# 08_USB3_0-RGMII.net
KiCad netlist of a schematic drawn in Altium Designer
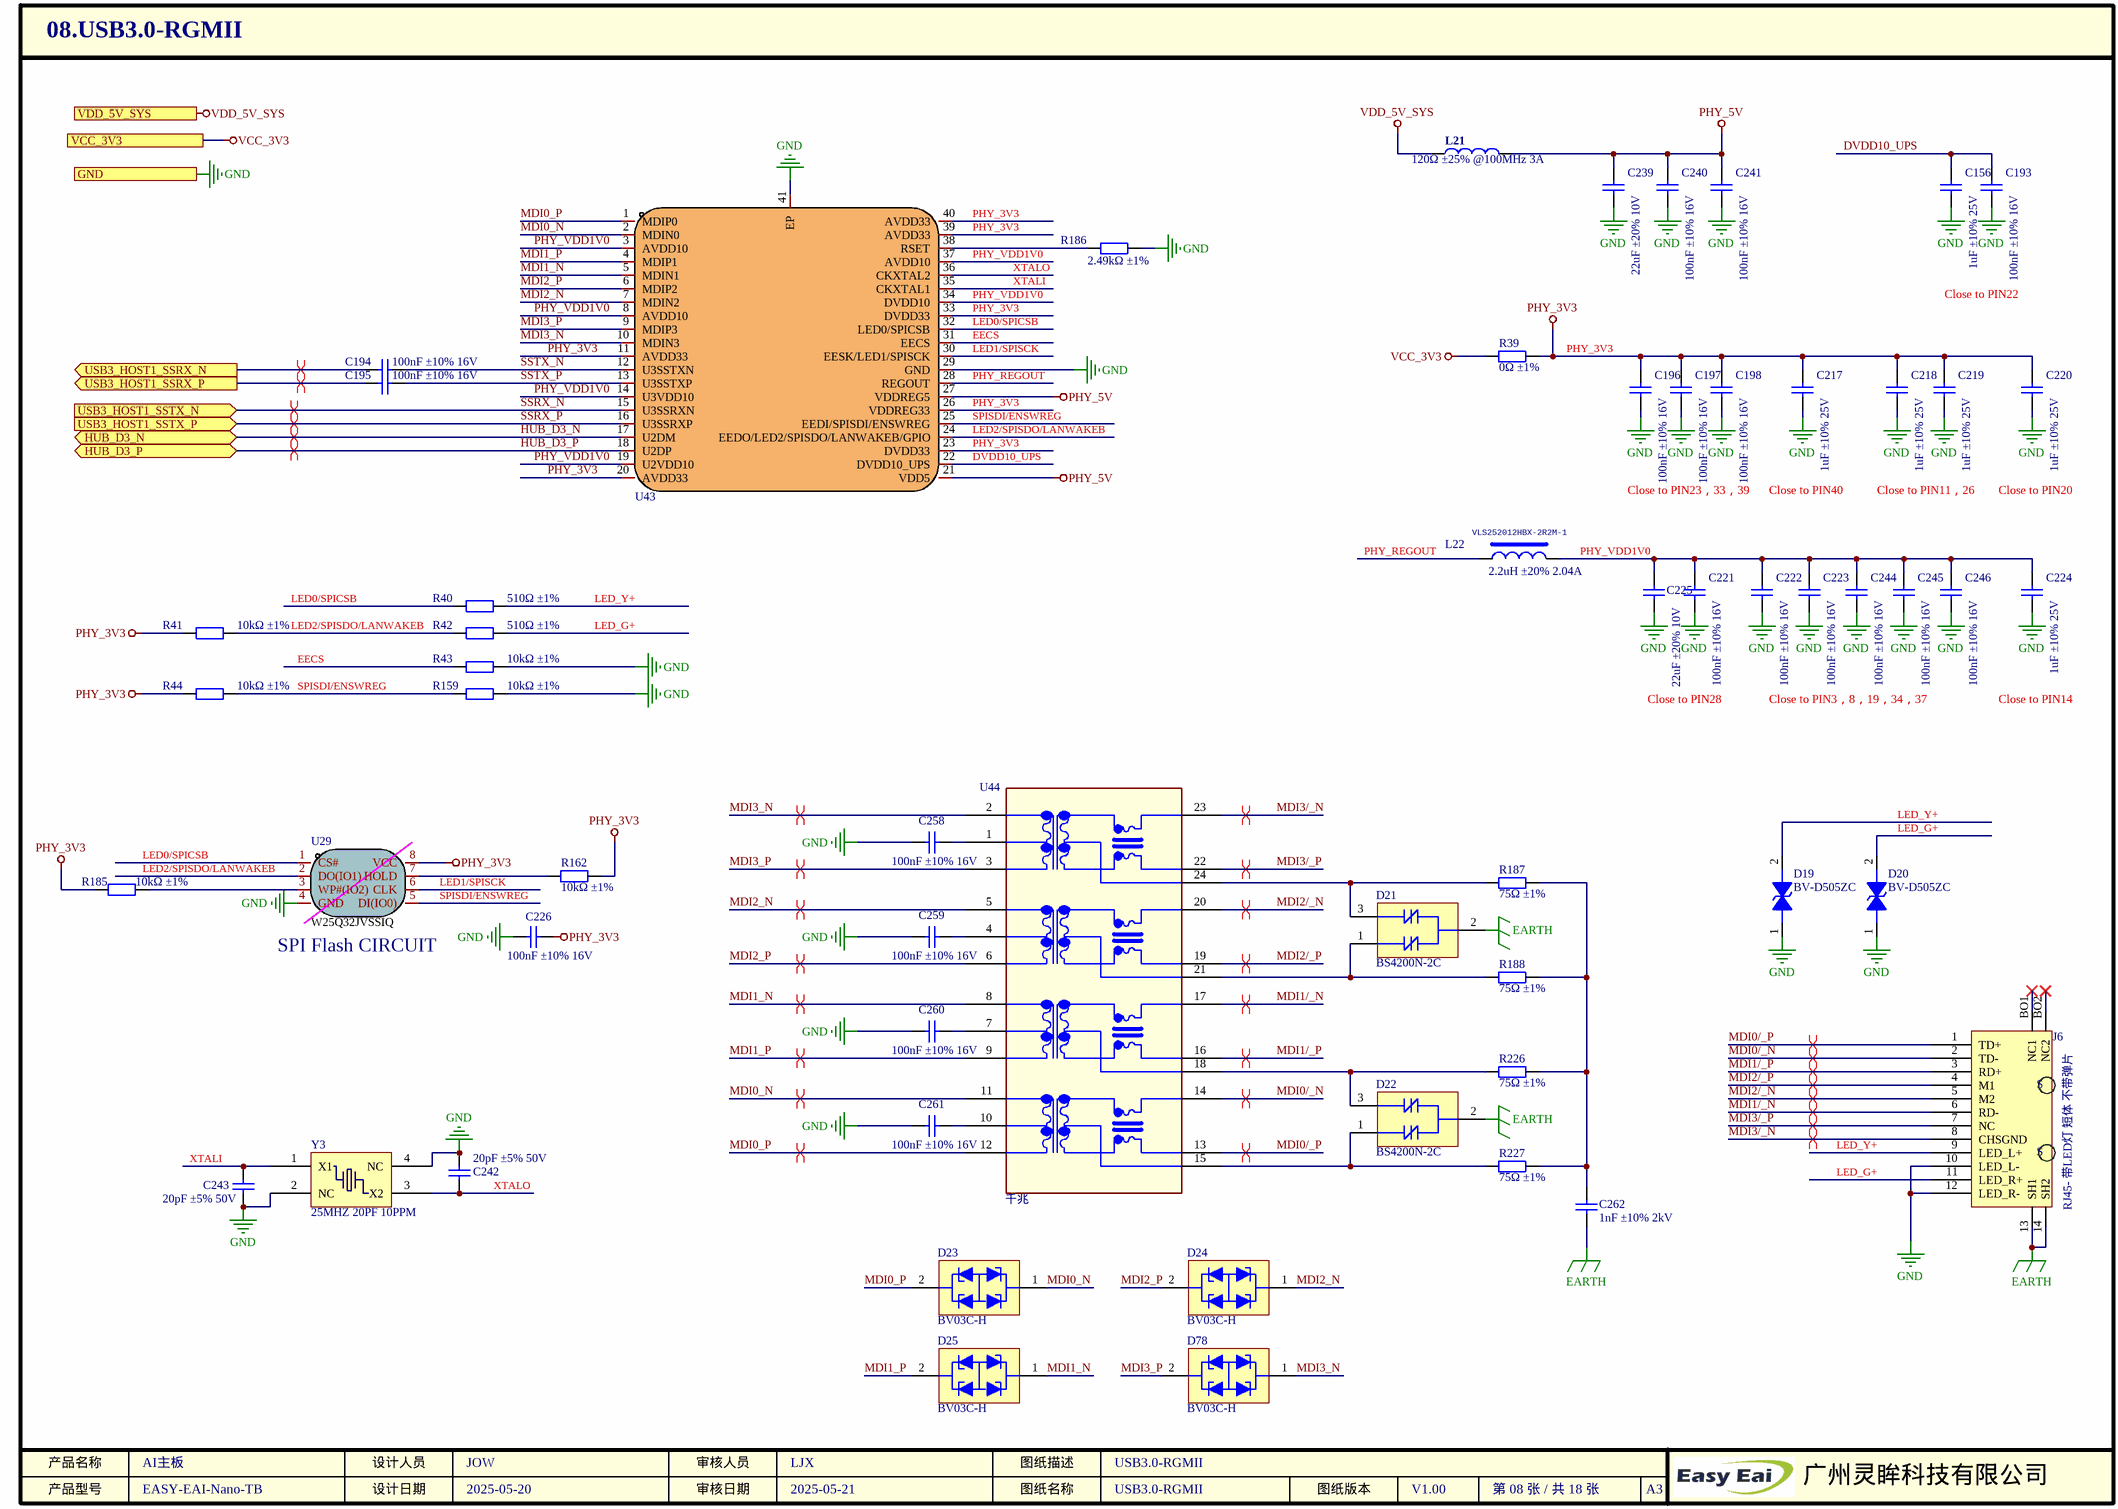
[diagram p0: 08.USB3.0-RGMII.SchDoc]

(export (version "E")
  (design (tool "Eeschema 10.0.6"))
  (components
    (comp (ref "C156")
      (value "CL05A105KA5NQNC")
      (footprint "0402_C")
      (description "SPZL000337")
      (fields (field (name "描述") "1uF ±10% 25V"))
      (libsource (lib "CAP_EASY-EAI") (part "0402 1uF ±10% 25V"))
    )
    (comp (ref "C193")
      (value "CL05B104KO5NNNC")
      (footprint "0402_C")
      (description "SPZL000259")
      (fields (field (name "描述") "100nF ±10% 16V"))
      (libsource (lib "CAP_lexing") (part "0402 100nF ±10% 16V"))
    )
    (comp (ref "C194")
      (value "CL05B104KO5NNNC")
      (footprint "0402_C")
      (description "SPZL000259")
      (fields (field (name "描述") "100nF ±10% 16V"))
      (libsource (lib "CAP_lexing") (part "0402 100nF ±10% 16V"))
    )
    (comp (ref "C195")
      (value "CL05B104KO5NNNC")
      (footprint "0402_C")
      (description "SPZL000259")
      (fields (field (name "描述") "100nF ±10% 16V"))
      (libsource (lib "CAP_lexing") (part "0402 100nF ±10% 16V"))
    )
    (comp (ref "C196")
      (value "CL05B104KO5NNNC")
      (footprint "0402_C")
      (description "SPZL000259")
      (fields (field (name "描述") "100nF ±10% 16V"))
      (libsource (lib "CAP_lexing") (part "0402 100nF ±10% 16V"))
    )
    (comp (ref "C197")
      (value "CL05B104KO5NNNC")
      (footprint "0402_C")
      (description "SPZL000259")
      (fields (field (name "描述") "100nF ±10% 16V"))
      (libsource (lib "CAP_lexing") (part "0402 100nF ±10% 16V"))
    )
    (comp (ref "C198")
      (value "CL05B104KO5NNNC")
      (footprint "0402_C")
      (description "SPZL000259")
      (fields (field (name "描述") "100nF ±10% 16V"))
      (libsource (lib "CAP_lexing") (part "0402 100nF ±10% 16V"))
    )
    (comp (ref "C217")
      (value "CL05A105KA5NQNC")
      (footprint "0402_C")
      (description "SPZL000337")
      (fields (field (name "描述") "1uF ±10% 25V"))
      (libsource (lib "CAP_EASY-EAI") (part "0402 1uF ±10% 25V"))
    )
    (comp (ref "C218")
      (value "CL05A105KA5NQNC")
      (footprint "0402_C")
      (description "SPZL000337")
      (fields (field (name "描述") "1uF ±10% 25V"))
      (libsource (lib "CAP_EASY-EAI") (part "0402 1uF ±10% 25V"))
    )
    (comp (ref "C219")
      (value "CL05A105KA5NQNC")
      (footprint "0402_C")
      (description "SPZL000337")
      (fields (field (name "描述") "1uF ±10% 25V"))
      (libsource (lib "CAP_EASY-EAI") (part "0402 1uF ±10% 25V"))
    )
    (comp (ref "C220")
      (value "CL05A105KA5NQNC")
      (footprint "0402_C")
      (description "SPZL000337")
      (fields (field (name "描述") "1uF ±10% 25V"))
      (libsource (lib "CAP_EASY-EAI") (part "0402 1uF ±10% 25V"))
    )
    (comp (ref "C221")
      (value "CL05B104KO5NNNC")
      (footprint "0402_C")
      (description "SPZL000259")
      (fields (field (name "描述") "100nF ±10% 16V"))
      (libsource (lib "CAP_lexing") (part "0402 100nF ±10% 16V"))
    )
    (comp (ref "C222")
      (value "CL05B104KO5NNNC")
      (footprint "0402_C")
      (description "SPZL000259")
      (fields (field (name "描述") "100nF ±10% 16V"))
      (libsource (lib "CAP_lexing") (part "0402 100nF ±10% 16V"))
    )
    (comp (ref "C223")
      (value "CL05B104KO5NNNC")
      (footprint "0402_C")
      (description "SPZL000259")
      (fields (field (name "描述") "100nF ±10% 16V"))
      (libsource (lib "CAP_lexing") (part "0402 100nF ±10% 16V"))
    )
    (comp (ref "C224")
      (value "CL05A105KA5NQNC")
      (footprint "0402_C")
      (description "SPZL000337")
      (fields (field (name "描述") "1uF ±10% 25V"))
      (libsource (lib "CAP_EASY-EAI") (part "0402 1uF ±10% 25V"))
    )
    (comp (ref "C225")
      (value "CL10A226MP8NUNE")
      (footprint "0603_C")
      (description "SPZL000315")
      (fields (field (name "描述") "22uF ±20% 10V"))
      (libsource (lib "CAP_lexing") (part "0603 22uF ±20% 10V"))
    )
    (comp (ref "C226")
      (value "CL05B104KO5NNNC")
      (footprint "0402_C")
      (description "SPZL000259")
      (fields (field (name "描述") "100nF ±10% 16V"))
      (libsource (lib "altium-import") (part "root_2_0402 100nF ±10% 16V_"))
    )
    (comp (ref "C239")
      (value "CL10A226MP8NUNE")
      (footprint "0603_C")
      (description "SPZL000315")
      (fields (field (name "描述") "22uF ±20% 10V"))
      (libsource (lib "CAP_lexing") (part "0603 22uF ±20% 10V"))
    )
    (comp (ref "C240")
      (value "CL05B104KO5NNNC")
      (footprint "0402_C")
      (description "SPZL000259")
      (fields (field (name "描述") "100nF ±10% 16V"))
      (libsource (lib "CAP_lexing") (part "0402 100nF ±10% 16V"))
    )
    (comp (ref "C241")
      (value "CL05B104KO5NNNC")
      (footprint "0402_C")
      (description "SPZL000259")
      (fields (field (name "描述") "100nF ±10% 16V"))
      (libsource (lib "CAP_lexing") (part "0402 100nF ±10% 16V"))
    )
    (comp (ref "C242")
      (value "0402CG200J500NT")
      (footprint "0402_C")
      (description "SPZL000398")
      (fields (field (name "描述") "20pF ±5% 50V"))
      (libsource (lib "CAP_lexing") (part "0402 20pF ±5% 50V"))
    )
    (comp (ref "C243")
      (value "0402CG200J500NT")
      (footprint "0402_C")
      (description "SPZL000398")
      (fields (field (name "描述") "20pF ±5% 50V"))
      (libsource (lib "CAP_lexing") (part "0402 20pF ±5% 50V"))
    )
    (comp (ref "C244")
      (value "CL05B104KO5NNNC")
      (footprint "0402_C")
      (description "SPZL000259")
      (fields (field (name "描述") "100nF ±10% 16V"))
      (libsource (lib "CAP_lexing") (part "0402 100nF ±10% 16V"))
    )
    (comp (ref "C245")
      (value "CL05B104KO5NNNC")
      (footprint "0402_C")
      (description "SPZL000259")
      (fields (field (name "描述") "100nF ±10% 16V"))
      (libsource (lib "CAP_lexing") (part "0402 100nF ±10% 16V"))
    )
    (comp (ref "C246")
      (value "CL05B104KO5NNNC")
      (footprint "0402_C")
      (description "SPZL000259")
      (fields (field (name "描述") "100nF ±10% 16V"))
      (libsource (lib "CAP_lexing") (part "0402 100nF ±10% 16V"))
    )
    (comp (ref "C258")
      (value "CL05B104KO5NNNC")
      (footprint "0402_C")
      (description "SPZL000259")
      (fields (field (name "描述") "100nF ±10% 16V"))
      (libsource (lib "CAP_lexing") (part "0402 100nF ±10% 16V"))
    )
    (comp (ref "C259")
      (value "CL05B104KO5NNNC")
      (footprint "0402_C")
      (description "SPZL000259")
      (fields (field (name "描述") "100nF ±10% 16V"))
      (libsource (lib "CAP_lexing") (part "0402 100nF ±10% 16V"))
    )
    (comp (ref "C260")
      (value "CL05B104KO5NNNC")
      (footprint "0402_C")
      (description "SPZL000259")
      (fields (field (name "描述") "100nF ±10% 16V"))
      (libsource (lib "CAP_lexing") (part "0402 100nF ±10% 16V"))
    )
    (comp (ref "C261")
      (value "CL05B104KO5NNNC")
      (footprint "0402_C")
      (description "SPZL000259")
      (fields (field (name "描述") "100nF ±10% 16V"))
      (libsource (lib "CAP_lexing") (part "0402 100nF ±10% 16V"))
    )
    (comp (ref "C262")
      (value "CC1206KKX7RDBB102")
      (footprint "1206_C")
      (description "SPZL000332")
      (fields (field (name "描述") "1nF ±10% 2kV"))
      (libsource (lib "CAP_lexing") (part "1206 1nF ±10% 2kV"))
    )
    (comp (ref "D19")
      (value "BV-D505ZC")
      (footprint "SOD-523")
      (description "SPZL000613")
      (fields (field (name "型号") "BV-D505ZC"))
      (libsource (lib "ESD_lexing") (part "ESD BV-D505ZC"))
    )
    (comp (ref "D20")
      (value "BV-D505ZC")
      (footprint "SOD-523")
      (description "SPZL000613")
      (fields (field (name "型号") "BV-D505ZC"))
      (libsource (lib "ESD_lexing") (part "ESD BV-D505ZC"))
    )
    (comp (ref "D21")
      (value "BS4200N-2C")
      (footprint "SMB-T_L5.4-W3.3-BI")
      (description "SPZL000612")
      (fields (field (name "型号") "BS4200N-2C"))
      (libsource (lib "ESD_lexing") (part "放电管 BS4200N-2C"))
    )
    (comp (ref "D22")
      (value "BS4200N-2C")
      (footprint "SMB-T_L5.4-W3.3-BI")
      (description "SPZL000612")
      (fields (field (name "型号") "BS4200N-2C"))
      (libsource (lib "ESD_lexing") (part "放电管 BS4200N-2C"))
    )
    (comp (ref "D23")
      (value "BV03C-H")
      (footprint "SOD-323")
      (description "SPZL000614")
      (fields (field (name "型号") "BV03C-H"))
      (libsource (lib "ESD_lexing") (part "ESD BV03C-H"))
    )
    (comp (ref "D24")
      (value "BV03C-H")
      (footprint "SOD-323")
      (description "SPZL000614")
      (fields (field (name "型号") "BV03C-H"))
      (libsource (lib "ESD_lexing") (part "ESD BV03C-H"))
    )
    (comp (ref "D25")
      (value "BV03C-H")
      (footprint "SOD-323")
      (description "SPZL000614")
      (fields (field (name "型号") "BV03C-H"))
      (libsource (lib "ESD_lexing") (part "ESD BV03C-H"))
    )
    (comp (ref "D78")
      (value "BV03C-H")
      (footprint "SOD-323")
      (description "SPZL000614")
      (fields (field (name "型号") "BV03C-H"))
      (libsource (lib "ESD_lexing") (part "ESD BV03C-H"))
    )
    (comp (ref "J6")
      (value "R-RJ45R08P-C000")
      (footprint "RJ45/LED-1575X1626X1310")
      (description "SPZL000140")
      (fields (field (name "描述") "RJ45- 带LED灯 短体 不带弹片"))
      (libsource (lib "EVBoard-RK3562") (part "RJ45- 带LED灯 短体 不带弹片"))
    )
    (comp (ref "L21")
      (value "BLM18KG121TN1D")
      (footprint "0603_R")
      (description "SPZL000842")
      (fields (field (name "描述") "120Ω ±25% @100MHz 3A"))
      (libsource (lib "Inductor_EASY-EAI") (part "120Ω ±25% @100MHz 3A"))
    )
    (comp (ref "L22")
      (value "VLS252012HBX-2R2M-1")
      (footprint "IND_252012")
      (description "SPZL000205")
      (fields (field (name "描述") "2.2uH ±20% 2.04A"))
      (libsource (lib "Inductor_EASY-EAI") (part "2.2uH ±20% 2.04A"))
    )
    (comp (ref "R39")
      (value "0805W8F0000T5E")
      (footprint "0805_R")
      (description "SPZL000350")
      (fields (field (name "描述") "0Ω ±1%"))
      (libsource (lib "RES_EASY-EAI") (part "0805 0Ω ±1%"))
    )
    (comp (ref "R40")
      (value "0402WGF5100TCE")
      (footprint "0402_R")
      (description "SPZL000335")
      (fields (field (name "描述") "510Ω ±1%"))
      (libsource (lib "RES_lexing") (part "0402 510Ω ±1%"))
    )
    (comp (ref "R41")
      (value "0402WGF1002TCE")
      (footprint "0402_R")
      (description "SPZL000271")
      (fields (field (name "描述") "10kΩ ±1%"))
      (libsource (lib "RES_EASY-EAI") (part "0402 10kΩ ±1%"))
    )
    (comp (ref "R42")
      (value "0402WGF5100TCE")
      (footprint "0402_R")
      (description "SPZL000335")
      (fields (field (name "描述") "510Ω ±1%"))
      (libsource (lib "RES_lexing") (part "0402 510Ω ±1%"))
    )
    (comp (ref "R43")
      (value "0402WGF1002TCE")
      (footprint "0402_R")
      (description "SPZL000271")
      (fields (field (name "描述") "10kΩ ±1%"))
      (libsource (lib "RES_EASY-EAI") (part "0402 10kΩ ±1%"))
    )
    (comp (ref "R44")
      (value "0402WGF1002TCE")
      (footprint "0402_R")
      (description "SPZL000271")
      (fields (field (name "描述") "10kΩ ±1%"))
      (libsource (lib "RES_EASY-EAI") (part "0402 10kΩ ±1%"))
    )
    (comp (ref "R159")
      (value "0402WGF1002TCE")
      (footprint "0402_R")
      (description "SPZL000271")
      (fields (field (name "描述") "10kΩ ±1%"))
      (libsource (lib "RES_EASY-EAI") (part "0402 10kΩ ±1%"))
    )
    (comp (ref "R162")
      (value "0402WGF1002TCE")
      (footprint "0402_R")
      (description "SPZL000271")
      (fields (field (name "描述") "10kΩ ±1%"))
      (libsource (lib "") (part "0402 10kΩ ±1%_1"))
    )
    (comp (ref "R185")
      (value "0402WGF1002TCE")
      (footprint "0402_R")
      (description "SPZL000271")
      (fields (field (name "描述") "10kΩ ±1%"))
      (libsource (lib "RES_EASY-EAI") (part "0402 10kΩ ±1%"))
    )
    (comp (ref "R186")
      (value "AC0402FR-072K49L")
      (footprint "0402_R")
      (description "SPZL000354")
      (fields (field (name "描述") "2.49kΩ ±1%"))
      (libsource (lib "RES_lexing") (part "0402 2.49kΩ ±1%"))
    )
    (comp (ref "R187")
      (value "RS-05K75R0FT")
      (footprint "0805_R")
      (description "SPZL000353")
      (fields (field (name "描述") "75Ω ±1%"))
      (libsource (lib "RES_lexing") (part "0805 75Ω ±1%"))
    )
    (comp (ref "R188")
      (value "RS-05K75R0FT")
      (footprint "0805_R")
      (description "SPZL000353")
      (fields (field (name "描述") "75Ω ±1%"))
      (libsource (lib "RES_lexing") (part "0805 75Ω ±1%"))
    )
    (comp (ref "R226")
      (value "RS-05K75R0FT")
      (footprint "0805_R")
      (description "SPZL000353")
      (fields (field (name "描述") "75Ω ±1%"))
      (libsource (lib "RES_lexing") (part "0805 75Ω ±1%"))
    )
    (comp (ref "R227")
      (value "RS-05K75R0FT")
      (footprint "0805_R")
      (description "SPZL000353")
      (fields (field (name "描述") "75Ω ±1%"))
      (libsource (lib "RES_lexing") (part "0805 75Ω ±1%"))
    )
    (comp (ref "U29")
      (value "W25Q32JVSSIQ")
      (footprint "SOIC-8-208mil")
      (description "SPZL001045")
      (fields (field (name "型号") "W25Q32JVSSIQ"))
      (libsource (lib "IC_EASY-EAI") (part "W25Q32JVSSIQ"))
    )
    (comp (ref "U43")
      (value "RTL8153B-VB-CG")
      (footprint "QFN-40_L5.0-W5.0-P0.40-BL-EP3.7")
      (description "SPZL001044")
      (libsource (lib "IC_lexing") (part "RTL8153B-VB-CG"))
    )
    (comp (ref "U44")
      (value "G2401CE")
      (footprint "SMD-24_L15.1-W7.1-P1.00-LS10.0-BL")
      (description "SPZL000720")
      (fields (field (name "描述") "千兆"))
      (libsource (lib "ESD_lexing") (part "网络变压器 G2401CE"))
    )
    (comp (ref "Y3")
      (value "X322525MSB4SI")
      (footprint "SMD-3225_4P")
      (description "SPZL000475")
      (fields (field (name "描述") "25MHZ 20PF 10PPM"))
      (libsource (lib "XTAL_lexing") (part "25MHZ 20PF 10PPM"))
    )
  )
  (nets
    (net (code "1") (name "/DVDD10_UPS") (class "Default")
      (node (ref "C156") (pin "2") (pinfunction "2_2") (pintype "passive"))
      (node (ref "C193") (pin "2") (pinfunction "2_2") (pintype "passive"))
      (node (ref "U43") (pin "22") (pinfunction "DVDD10_UPS_22") (pintype "passive"))
    )
    (net (code "2") (name "/EECS") (class "Default")
      (node (ref "R43") (pin "2") (pinfunction "2_2") (pintype "passive"))
      (node (ref "U43") (pin "31") (pinfunction "EECS_31") (pintype "passive"))
    )
    (net (code "3") (name "/HUB_D3_N") (class "Default")
      (node (ref "U43") (pin "17") (pinfunction "U2DM_17") (pintype "passive"))
    )
    (net (code "4") (name "/HUB_D3_P") (class "Default")
      (node (ref "U43") (pin "18") (pinfunction "U2DP_18") (pintype "passive"))
    )
    (net (code "5") (name "/LED0{slash}SPICSB") (class "Default")
      (node (ref "R40") (pin "1") (pinfunction "1_1") (pintype "passive"))
      (node (ref "U29") (pin "1") (pinfunction "CS#_1") (pintype "passive"))
      (node (ref "U43") (pin "32") (pinfunction "LED0/SPICSB_32") (pintype "passive"))
    )
    (net (code "6") (name "/LED1{slash}SPISCK") (class "Default")
      (node (ref "U29") (pin "6") (pinfunction "CLK_6") (pintype "passive"))
      (node (ref "U43") (pin "30") (pinfunction "EESK/LED1/SPISCK_30") (pintype "passive"))
    )
    (net (code "7") (name "/LED2{slash}SPISDO{slash}LANWAKEB") (class "Default")
      (node (ref "R41") (pin "1") (pinfunction "1_1") (pintype "passive"))
      (node (ref "R42") (pin "1") (pinfunction "1_1") (pintype "passive"))
      (node (ref "U29") (pin "2") (pinfunction "DO(IO1)_2") (pintype "passive"))
      (node (ref "U43") (pin "24") (pinfunction "EEDO/LED2/SPISDO/LANWAKEB/GPIO_24") (pintype "passive"))
    )
    (net (code "8") (name "/LED_G+") (class "Default")
      (node (ref "D20") (pin "2") (pinfunction "2_2") (pintype "passive"))
      (node (ref "J6") (pin "11") (pinfunction "LED_R+_11") (pintype "passive"))
      (node (ref "R42") (pin "2") (pinfunction "2_2") (pintype "passive"))
    )
    (net (code "9") (name "/LED_Y+") (class "Default")
      (node (ref "D19") (pin "2") (pinfunction "2_2") (pintype "passive"))
      (node (ref "J6") (pin "9") (pinfunction "LED_L+_9") (pintype "passive"))
      (node (ref "R40") (pin "2") (pinfunction "2_2") (pintype "passive"))
    )
    (net (code "10") (name "/MDI0_N") (class "Default")
      (node (ref "D23") (pin "1") (pintype "passive"))
      (node (ref "U43") (pin "2") (pinfunction "MDIN0_2") (pintype "passive"))
      (node (ref "U44") (pin "11") (pinfunction "11_11") (pintype "passive"))
    )
    (net (code "11") (name "/MDI0_P") (class "Default")
      (node (ref "D23") (pin "2") (pintype "passive"))
      (node (ref "U43") (pin "1") (pinfunction "MDIP0_1") (pintype "passive"))
      (node (ref "U44") (pin "12") (pinfunction "12_12") (pintype "passive"))
    )
    (net (code "12") (name "/MDI0{slash}_N") (class "Default")
      (node (ref "J6") (pin "2") (pinfunction "TD-_2") (pintype "passive"))
      (node (ref "U44") (pin "14") (pinfunction "14_14") (pintype "passive"))
    )
    (net (code "13") (name "/MDI0{slash}_P") (class "Default")
      (node (ref "J6") (pin "1") (pinfunction "TD+_1") (pintype "passive"))
      (node (ref "U44") (pin "13") (pinfunction "13_13") (pintype "passive"))
    )
    (net (code "14") (name "/MDI1_N") (class "Default")
      (node (ref "D25") (pin "1") (pintype "passive"))
      (node (ref "U43") (pin "5") (pinfunction "MDIN1_5") (pintype "passive"))
      (node (ref "U44") (pin "8") (pinfunction "8_8") (pintype "passive"))
    )
    (net (code "15") (name "/MDI1_P") (class "Default")
      (node (ref "D25") (pin "2") (pintype "passive"))
      (node (ref "U43") (pin "4") (pinfunction "MDIP1_4") (pintype "passive"))
      (node (ref "U44") (pin "9") (pinfunction "9_9") (pintype "passive"))
    )
    (net (code "16") (name "/MDI1{slash}_N") (class "Default")
      (node (ref "J6") (pin "6") (pinfunction "RD-_6") (pintype "passive"))
      (node (ref "U44") (pin "17") (pinfunction "17_17") (pintype "passive"))
    )
    (net (code "17") (name "/MDI1{slash}_P") (class "Default")
      (node (ref "J6") (pin "3") (pinfunction "RD+_3") (pintype "passive"))
      (node (ref "U44") (pin "16") (pinfunction "16_16") (pintype "passive"))
    )
    (net (code "18") (name "/MDI2_N") (class "Default")
      (node (ref "D24") (pin "1") (pintype "passive"))
      (node (ref "U43") (pin "7") (pinfunction "MDIN2_7") (pintype "passive"))
      (node (ref "U44") (pin "5") (pinfunction "5_5") (pintype "passive"))
    )
    (net (code "19") (name "/MDI2_P") (class "Default")
      (node (ref "D24") (pin "2") (pintype "passive"))
      (node (ref "U43") (pin "6") (pinfunction "MDIP2_6") (pintype "passive"))
      (node (ref "U44") (pin "6") (pinfunction "6_6") (pintype "passive"))
    )
    (net (code "20") (name "/MDI2{slash}_N") (class "Default")
      (node (ref "J6") (pin "5") (pinfunction "M2_5") (pintype "passive"))
      (node (ref "U44") (pin "20") (pinfunction "20_20") (pintype "passive"))
    )
    (net (code "21") (name "/MDI2{slash}_P") (class "Default")
      (node (ref "J6") (pin "4") (pinfunction "M1_4") (pintype "passive"))
      (node (ref "U44") (pin "19") (pinfunction "19_19") (pintype "passive"))
    )
    (net (code "22") (name "/MDI3_N") (class "Default")
      (node (ref "D78") (pin "1") (pintype "passive"))
      (node (ref "U43") (pin "10") (pinfunction "MDIN3_10") (pintype "passive"))
      (node (ref "U44") (pin "2") (pinfunction "2_2") (pintype "passive"))
    )
    (net (code "23") (name "/MDI3_P") (class "Default")
      (node (ref "D78") (pin "2") (pintype "passive"))
      (node (ref "U43") (pin "9") (pinfunction "MDIP3_9") (pintype "passive"))
      (node (ref "U44") (pin "3") (pinfunction "3_3") (pintype "passive"))
    )
    (net (code "24") (name "/MDI3{slash}_N") (class "Default")
      (node (ref "J6") (pin "8") (pinfunction "CHSGND_8") (pintype "passive"))
      (node (ref "U44") (pin "23") (pinfunction "23_23") (pintype "passive"))
    )
    (net (code "25") (name "/MDI3{slash}_P") (class "Default")
      (node (ref "J6") (pin "7") (pinfunction "NC_7") (pintype "passive"))
      (node (ref "U44") (pin "22") (pinfunction "22_22") (pintype "passive"))
    )
    (net (code "26") (name "/PHY_REGOUT") (class "Default")
      (node (ref "L22") (pin "1") (pinfunction "1_1") (pintype "passive"))
      (node (ref "U43") (pin "28") (pinfunction "REGOUT_28") (pintype "passive"))
    )
    (net (code "27") (name "/PHY_VDD1V0") (class "Default")
      (node (ref "C221") (pin "2") (pinfunction "2_2") (pintype "passive"))
      (node (ref "C222") (pin "2") (pinfunction "2_2") (pintype "passive"))
      (node (ref "C223") (pin "2") (pinfunction "2_2") (pintype "passive"))
      (node (ref "C224") (pin "2") (pinfunction "2_2") (pintype "passive"))
      (node (ref "C225") (pin "2") (pinfunction "2_2") (pintype "passive"))
      (node (ref "C244") (pin "2") (pinfunction "2_2") (pintype "passive"))
      (node (ref "C245") (pin "2") (pinfunction "2_2") (pintype "passive"))
      (node (ref "C246") (pin "2") (pinfunction "2_2") (pintype "passive"))
      (node (ref "L22") (pin "2") (pinfunction "2_2") (pintype "passive"))
      (node (ref "U43") (pin "14") (pinfunction "U3VDD10_14") (pintype "passive"))
      (node (ref "U43") (pin "19") (pinfunction "U2VDD10_19") (pintype "passive"))
      (node (ref "U43") (pin "3") (pinfunction "AVDD10_3") (pintype "passive"))
      (node (ref "U43") (pin "34") (pinfunction "DVDD10_34") (pintype "passive"))
      (node (ref "U43") (pin "37") (pinfunction "AVDD10_37") (pintype "passive"))
      (node (ref "U43") (pin "8") (pinfunction "AVDD10_8") (pintype "passive"))
    )
    (net (code "28") (name "/SPISDI{slash}ENSWREG") (class "Default")
      (node (ref "R159") (pin "2") (pinfunction "2_2") (pintype "passive"))
      (node (ref "R44") (pin "1") (pinfunction "1_1") (pintype "passive"))
      (node (ref "U29") (pin "5") (pinfunction "DI(IO0)_5") (pintype "passive"))
      (node (ref "U43") (pin "25") (pinfunction "EEDI/SPISDI/ENSWREG_25") (pintype "passive"))
    )
    (net (code "29") (name "/SSRX_N") (class "Default")
      (node (ref "U43") (pin "15") (pinfunction "U3SSRXN_15") (pintype "passive"))
    )
    (net (code "30") (name "/SSRX_P") (class "Default")
      (node (ref "U43") (pin "16") (pinfunction "U3SSRXP_16") (pintype "passive"))
    )
    (net (code "31") (name "/SSTX_N") (class "Default")
      (node (ref "C194") (pin "2") (pinfunction "2_2") (pintype "passive"))
      (node (ref "U43") (pin "12") (pinfunction "U3SSTXN_12") (pintype "passive"))
    )
    (net (code "32") (name "/SSTX_P") (class "Default")
      (node (ref "C195") (pin "2") (pinfunction "2_2") (pintype "passive"))
      (node (ref "U43") (pin "13") (pinfunction "U3SSTXP_13") (pintype "passive"))
    )
    (net (code "33") (name "/USB3_HOST1_SSRX_N") (class "Default")
      (node (ref "C194") (pin "1") (pinfunction "1_1") (pintype "passive"))
    )
    (net (code "34") (name "/USB3_HOST1_SSRX_P") (class "Default")
      (node (ref "C195") (pin "1") (pinfunction "1_1") (pintype "passive"))
    )
    (net (code "35") (name "/XTALI") (class "Default")
      (node (ref "C243") (pin "2") (pinfunction "2_2") (pintype "passive"))
      (node (ref "U43") (pin "35") (pinfunction "CKXTAL1_35") (pintype "passive"))
      (node (ref "Y3") (pin "1") (pinfunction "X1_1") (pintype "passive"))
    )
    (net (code "36") (name "/XTALO") (class "Default")
      (node (ref "C242") (pin "1") (pinfunction "1_1") (pintype "passive"))
      (node (ref "U43") (pin "36") (pinfunction "CKXTAL2_36") (pintype "passive"))
      (node (ref "Y3") (pin "3") (pinfunction "X2_3") (pintype "passive"))
    )
    (net (code "37") (name "EARTH") (class "Default")
      (node (ref "C262") (pin "1") (pinfunction "1_1") (pintype "passive"))
      (node (ref "D21") (pin "2") (pintype "passive"))
      (node (ref "D22") (pin "2") (pintype "passive"))
      (node (ref "J6") (pin "13") (pinfunction "SH1_13") (pintype "passive"))
      (node (ref "J6") (pin "14") (pinfunction "SH2_14") (pintype "passive"))
    )
    (net (code "38") (name "GND") (class "Default")
      (node (ref "C156") (pin "1") (pinfunction "1_1") (pintype "passive"))
      (node (ref "C193") (pin "1") (pinfunction "1_1") (pintype "passive"))
      (node (ref "C196") (pin "1") (pinfunction "1_1") (pintype "passive"))
      (node (ref "C197") (pin "1") (pinfunction "1_1") (pintype "passive"))
      (node (ref "C198") (pin "1") (pinfunction "1_1") (pintype "passive"))
      (node (ref "C217") (pin "1") (pinfunction "1_1") (pintype "passive"))
      (node (ref "C218") (pin "1") (pinfunction "1_1") (pintype "passive"))
      (node (ref "C219") (pin "1") (pinfunction "1_1") (pintype "passive"))
      (node (ref "C220") (pin "1") (pinfunction "1_1") (pintype "passive"))
      (node (ref "C221") (pin "1") (pinfunction "1_1") (pintype "passive"))
      (node (ref "C222") (pin "1") (pinfunction "1_1") (pintype "passive"))
      (node (ref "C223") (pin "1") (pinfunction "1_1") (pintype "passive"))
      (node (ref "C224") (pin "1") (pinfunction "1_1") (pintype "passive"))
      (node (ref "C225") (pin "1") (pinfunction "1_1") (pintype "passive"))
      (node (ref "C226") (pin "2") (pinfunction "2_2") (pintype "passive"))
      (node (ref "C239") (pin "1") (pinfunction "1_1") (pintype "passive"))
      (node (ref "C240") (pin "1") (pinfunction "1_1") (pintype "passive"))
      (node (ref "C241") (pin "1") (pinfunction "1_1") (pintype "passive"))
      (node (ref "C242") (pin "2") (pinfunction "2_2") (pintype "passive"))
      (node (ref "C243") (pin "1") (pinfunction "1_1") (pintype "passive"))
      (node (ref "C244") (pin "1") (pinfunction "1_1") (pintype "passive"))
      (node (ref "C245") (pin "1") (pinfunction "1_1") (pintype "passive"))
      (node (ref "C246") (pin "1") (pinfunction "1_1") (pintype "passive"))
      (node (ref "C258") (pin "1") (pinfunction "1_1") (pintype "passive"))
      (node (ref "C259") (pin "1") (pinfunction "1_1") (pintype "passive"))
      (node (ref "C260") (pin "1") (pinfunction "1_1") (pintype "passive"))
      (node (ref "C261") (pin "1") (pinfunction "1_1") (pintype "passive"))
      (node (ref "D19") (pin "1") (pinfunction "1_1") (pintype "passive"))
      (node (ref "D20") (pin "1") (pinfunction "1_1") (pintype "passive"))
      (node (ref "J6") (pin "10") (pinfunction "LED_L-_10") (pintype "passive"))
      (node (ref "J6") (pin "12") (pinfunction "LED_R-_12") (pintype "passive"))
      (node (ref "R159") (pin "1") (pinfunction "1_1") (pintype "passive"))
      (node (ref "R186") (pin "2") (pinfunction "2_2") (pintype "passive"))
      (node (ref "R43") (pin "1") (pinfunction "1_1") (pintype "passive"))
      (node (ref "U29") (pin "4") (pinfunction "GND_4") (pintype "passive"))
      (node (ref "U43") (pin "29") (pinfunction "GND_29") (pintype "passive"))
      (node (ref "U43") (pin "41") (pinfunction "EP_41") (pintype "passive"))
      (node (ref "Y3") (pin "2") (pinfunction "NC_2") (pintype "passive"))
      (node (ref "Y3") (pin "4") (pinfunction "NC_4") (pintype "passive"))
    )
    (net (code "39") (name "Net-(C258-Pad2)") (class "Default")
      (node (ref "C258") (pin "2") (pinfunction "2_2") (pintype "passive"))
      (node (ref "U44") (pin "1") (pinfunction "1_1") (pintype "passive"))
    )
    (net (code "40") (name "Net-(C259-Pad2)") (class "Default")
      (node (ref "C259") (pin "2") (pinfunction "2_2") (pintype "passive"))
      (node (ref "U44") (pin "4") (pinfunction "4_4") (pintype "passive"))
    )
    (net (code "41") (name "Net-(C260-Pad2)") (class "Default")
      (node (ref "C260") (pin "2") (pinfunction "2_2") (pintype "passive"))
      (node (ref "U44") (pin "7") (pinfunction "7_7") (pintype "passive"))
    )
    (net (code "42") (name "Net-(C261-Pad2)") (class "Default")
      (node (ref "C261") (pin "2") (pinfunction "2_2") (pintype "passive"))
      (node (ref "U44") (pin "10") (pinfunction "10_10") (pintype "passive"))
    )
    (net (code "43") (name "Net-(C262-Pad2)") (class "Default")
      (node (ref "C262") (pin "2") (pinfunction "2_2") (pintype "passive"))
      (node (ref "R187") (pin "2") (pinfunction "2_2") (pintype "passive"))
      (node (ref "R188") (pin "2") (pinfunction "2_2") (pintype "passive"))
      (node (ref "R226") (pin "2") (pinfunction "2_2") (pintype "passive"))
      (node (ref "R227") (pin "2") (pinfunction "2_2") (pintype "passive"))
    )
    (net (code "44") (name "Net-(D21-Pad1)") (class "Default")
      (node (ref "D21") (pin "1") (pintype "passive"))
      (node (ref "R188") (pin "1") (pinfunction "1_1") (pintype "passive"))
      (node (ref "U44") (pin "21") (pinfunction "21_21") (pintype "passive"))
    )
    (net (code "45") (name "Net-(D21-Pad3)") (class "Default")
      (node (ref "D21") (pin "3") (pintype "passive"))
      (node (ref "R187") (pin "1") (pinfunction "1_1") (pintype "passive"))
      (node (ref "U44") (pin "24") (pinfunction "24_24") (pintype "passive"))
    )
    (net (code "46") (name "Net-(D22-Pad1)") (class "Default")
      (node (ref "D22") (pin "1") (pintype "passive"))
      (node (ref "R227") (pin "1") (pinfunction "1_1") (pintype "passive"))
      (node (ref "U44") (pin "15") (pinfunction "15_15") (pintype "passive"))
    )
    (net (code "47") (name "Net-(D22-Pad3)") (class "Default")
      (node (ref "D22") (pin "3") (pintype "passive"))
      (node (ref "R226") (pin "1") (pinfunction "1_1") (pintype "passive"))
      (node (ref "U44") (pin "18") (pinfunction "18_18") (pintype "passive"))
    )
    (net (code "48") (name "Net-(U29-HOLD)") (class "Default")
      (node (ref "R162") (pin "1") (pinfunction "1_1") (pintype "passive"))
      (node (ref "U29") (pin "7") (pinfunction "HOLD_7") (pintype "passive"))
    )
    (net (code "49") (name "Net-(U29-WP#(IO2))") (class "Default")
      (node (ref "R185") (pin "1") (pinfunction "1_1") (pintype "passive"))
      (node (ref "U29") (pin "3") (pinfunction "WP#(IO2)_3") (pintype "passive"))
    )
    (net (code "50") (name "Net-(U43-RSET)") (class "Default")
      (node (ref "R186") (pin "1") (pinfunction "1_1") (pintype "passive"))
      (node (ref "U43") (pin "38") (pinfunction "RSET_38") (pintype "passive"))
    )
    (net (code "51") (name "PHY_3V3") (class "Default")
      (node (ref "C196") (pin "2") (pinfunction "2_2") (pintype "passive"))
      (node (ref "C197") (pin "2") (pinfunction "2_2") (pintype "passive"))
      (node (ref "C198") (pin "2") (pinfunction "2_2") (pintype "passive"))
      (node (ref "C217") (pin "2") (pinfunction "2_2") (pintype "passive"))
      (node (ref "C218") (pin "2") (pinfunction "2_2") (pintype "passive"))
      (node (ref "C219") (pin "2") (pinfunction "2_2") (pintype "passive"))
      (node (ref "C220") (pin "2") (pinfunction "2_2") (pintype "passive"))
      (node (ref "C226") (pin "1") (pinfunction "1_1") (pintype "passive"))
      (node (ref "R162") (pin "2") (pinfunction "2_2") (pintype "passive"))
      (node (ref "R185") (pin "2") (pinfunction "2_2") (pintype "passive"))
      (node (ref "R39") (pin "2") (pinfunction "2_2") (pintype "passive"))
      (node (ref "R41") (pin "2") (pinfunction "2_2") (pintype "passive"))
      (node (ref "R44") (pin "2") (pinfunction "2_2") (pintype "passive"))
      (node (ref "U29") (pin "8") (pinfunction "VCC_8") (pintype "passive"))
      (node (ref "U43") (pin "11") (pinfunction "AVDD33_11") (pintype "passive"))
      (node (ref "U43") (pin "20") (pinfunction "AVDD33_20") (pintype "passive"))
      (node (ref "U43") (pin "23") (pinfunction "DVDD33_23") (pintype "passive"))
      (node (ref "U43") (pin "26") (pinfunction "VDDREG33_26") (pintype "passive"))
      (node (ref "U43") (pin "33") (pinfunction "DVDD33_33") (pintype "passive"))
      (node (ref "U43") (pin "39") (pinfunction "AVDD33_39") (pintype "passive"))
      (node (ref "U43") (pin "40") (pinfunction "AVDD33_40") (pintype "passive"))
    )
    (net (code "52") (name "PHY_5V") (class "Default")
      (node (ref "C239") (pin "2") (pinfunction "2_2") (pintype "passive"))
      (node (ref "C240") (pin "2") (pinfunction "2_2") (pintype "passive"))
      (node (ref "C241") (pin "2") (pinfunction "2_2") (pintype "passive"))
      (node (ref "L21") (pin "2") (pinfunction "2_2") (pintype "passive"))
      (node (ref "U43") (pin "21") (pinfunction "VDD5_21") (pintype "passive"))
      (node (ref "U43") (pin "27") (pinfunction "VDDREG5_27") (pintype "passive"))
    )
    (net (code "53") (name "VCC_3V3") (class "Default")
      (node (ref "R39") (pin "1") (pinfunction "1_1") (pintype "passive"))
    )
    (net (code "54") (name "VDD_5V_SYS") (class "Default")
      (node (ref "L21") (pin "1") (pinfunction "1_1") (pintype "passive"))
    )
    (net (code "55") (name "unconnected-(J6-NC1-PadBO1)") (class "Default")
      (node (ref "J6") (pin "BO1") (pinfunction "NC1_BO1") (pintype "passive+no_connect"))
    )
    (net (code "56") (name "unconnected-(J6-NC2-PadBO2)") (class "Default")
      (node (ref "J6") (pin "BO2") (pinfunction "NC2_BO2") (pintype "passive+no_connect"))
    )
  )
)
